# AD8367.net
KiCad netlist of a schematic drawn in Altium Designer
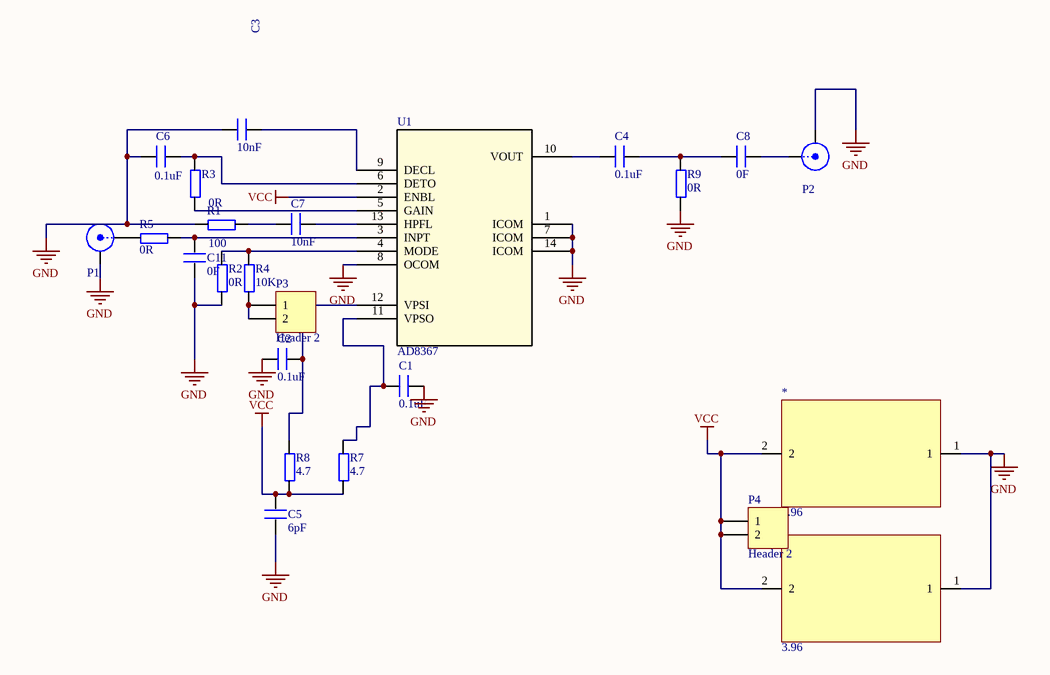
[diagram p0: AD8367.SchDoc]

(export (version "E")
  (design (tool "Eeschema 10.0.6"))
  (components
    (comp (ref "*") (value "3.96") (footprint "3.96") (libsource (lib "MYLIB") (part "3.96")))
    (comp (ref "1") (value "3.96") (footprint "3.96") (libsource (lib "MYLIB") (part "3.96")))
    (comp (ref "C1")
      (value "0.1uF")
      (footprint "0603C")
      (description "Capacitor")
      (libsource (lib "MYLIB") (part "C"))
    )
    (comp (ref "C2")
      (value "0.1uF")
      (footprint "0603C")
      (description "Capacitor")
      (libsource (lib "MYLIB") (part "C"))
    )
    (comp (ref "C3")
      (value "10nF")
      (footprint "0603C")
      (description "Capacitor")
      (libsource (lib "MYLIB") (part "C"))
    )
    (comp (ref "C4")
      (value "0.1uF")
      (footprint "0603C")
      (description "Capacitor")
      (libsource (lib "MYLIB") (part "C"))
    )
    (comp (ref "C5")
      (value "6pF")
      (footprint "C 0805_M")
      (description "Capacitor")
      (libsource (lib "MYLIB") (part "C"))
    )
    (comp (ref "C6")
      (value "0.1uF")
      (footprint "0603C")
      (description "Capacitor")
      (libsource (lib "MYLIB") (part "C"))
    )
    (comp (ref "C7")
      (value "10nF")
      (footprint "0603C")
      (description "Capacitor")
      (libsource (lib "MYLIB") (part "C"))
    )
    (comp (ref "C8")
      (value "0F")
      (footprint "0603C")
      (description "Capacitor")
      (libsource (lib "MYLIB") (part "C"))
    )
    (comp (ref "C11")
      (value "0F")
      (footprint "0603C")
      (description "Capacitor")
      (libsource (lib "MYLIB") (part "C"))
    )
    (comp (ref "P1")
      (value "SMA")
      (footprint "SMA-V")
      (description "SMA Connector")
      (libsource (lib "MYLIB") (part "SMA"))
    )
    (comp (ref "P2")
      (value "SMA")
      (footprint "SMA-V")
      (description "SMA Connector")
      (libsource (lib "MYLIB") (part "SMA"))
    )
    (comp (ref "P3")
      (value "Header 2")
      (footprint "HDR1X2")
      (description "Header, 2-Pin")
      (fields (field (name "PUBLISHER") "Altium Limited"))
      (libsource (lib "Miscellaneous Connectors") (part "Header 2"))
    )
    (comp (ref "P4")
      (value "Header 2")
      (footprint "HDR1X2")
      (description "Header, 2-Pin")
      (fields (field (name "PUBLISHER") "Altium Limited"))
      (libsource (lib "Miscellaneous Connectors") (part "Header 2"))
    )
    (comp (ref "R1")
      (value "100")
      (footprint "0603R")
      (description "Resistor")
      (libsource (lib "MYLIB") (part "Resistor"))
    )
    (comp (ref "R2")
      (value "0R")
      (footprint "0603R")
      (description "Resistor")
      (libsource (lib "MYLIB") (part "Resistor"))
    )
    (comp (ref "R3")
      (value "0R")
      (footprint "0603R")
      (description "Resistor")
      (libsource (lib "MYLIB") (part "Resistor"))
    )
    (comp (ref "R4")
      (value "10K")
      (footprint "0603R")
      (description "Resistor")
      (libsource (lib "MYLIB") (part "Resistor"))
    )
    (comp (ref "R5")
      (value "0R")
      (footprint "0603R")
      (description "Resistor")
      (libsource (lib "MYLIB") (part "Resistor"))
    )
    (comp (ref "R7")
      (value "4.7")
      (footprint "0603R")
      (description "Resistor")
      (libsource (lib "MYLIB") (part "Resistor"))
    )
    (comp (ref "R8")
      (value "4.7")
      (footprint "0603R")
      (description "Resistor")
      (libsource (lib "MYLIB") (part "Resistor"))
    )
    (comp (ref "R9")
      (value "0R")
      (footprint "0603R")
      (description "Resistor")
      (libsource (lib "MYLIB") (part "Resistor"))
    )
    (comp (ref "U1")
      (value "AD8367")
      (footprint "RU_14")
      (description "500 MHz 、45dB线性dB可变增益放大器")
      (fields
        (field (name "MANUFACTURER_PART_NUMBER") "AD8367ARUZ")
        (field (name "COPYRIGHT") "Copyright (C) 2018 Accelerated Designs. All rights reserved")
      )
      (libsource (lib "MYLIB") (part "AD8367"))
    )
  )
  (nets
    (net (code "1") (name "GND") (class "Default")
      (node (ref "*") (pin "1") (pinfunction "1_1") (pintype "passive"))
      (node (ref "1") (pin "1") (pinfunction "1_1") (pintype "passive"))
      (node (ref "C1") (pin "1") (pintype "passive"))
      (node (ref "C11") (pin "2") (pintype "passive"))
      (node (ref "C2") (pin "2") (pintype "passive"))
      (node (ref "C3") (pin "1") (pintype "passive"))
      (node (ref "C5") (pin "1") (pintype "passive"))
      (node (ref "C6") (pin "1") (pintype "passive"))
      (node (ref "P1") (pin "2") (pinfunction "Y_2") (pintype "passive"))
      (node (ref "P2") (pin "2") (pinfunction "Y_2") (pintype "passive"))
      (node (ref "R1") (pin "1") (pintype "passive"))
      (node (ref "R2") (pin "1") (pintype "passive"))
      (node (ref "R9") (pin "1") (pintype "passive"))
      (node (ref "U1") (pin "1") (pinfunction "ICOM_1") (pintype "passive"))
      (node (ref "U1") (pin "14") (pinfunction "ICOM_14") (pintype "passive"))
      (node (ref "U1") (pin "7") (pinfunction "ICOM_7") (pintype "passive"))
      (node (ref "U1") (pin "8") (pinfunction "OCOM_8") (pintype "passive"))
    )
    (net (code "2") (name "Net-(C4-Pad2)") (class "Default")
      (node (ref "C4") (pin "2") (pintype "passive"))
      (node (ref "C8") (pin "1") (pintype "passive"))
      (node (ref "R9") (pin "2") (pintype "passive"))
    )
    (net (code "3") (name "Net-(C7-Pad1)") (class "Default")
      (node (ref "C7") (pin "1") (pintype "passive"))
      (node (ref "R1") (pin "2") (pintype "passive"))
    )
    (net (code "4") (name "Net-(P1-X)") (class "Default")
      (node (ref "P1") (pin "1") (pinfunction "X_1") (pintype "passive"))
      (node (ref "R5") (pin "1") (pintype "passive"))
    )
    (net (code "5") (name "Net-(P2-X)") (class "Default")
      (node (ref "C8") (pin "2") (pintype "passive"))
      (node (ref "P2") (pin "1") (pinfunction "X_1") (pintype "passive"))
    )
    (net (code "6") (name "Net-(P3-Pad1)") (class "Default")
      (node (ref "P3") (pin "1") (pinfunction "1_1") (pintype "passive"))
      (node (ref "P3") (pin "2") (pinfunction "2_2") (pintype "passive"))
      (node (ref "R4") (pin "1") (pintype "passive"))
    )
    (net (code "7") (name "Net-(U1-DECL)") (class "Default")
      (node (ref "C3") (pin "2") (pintype "passive"))
      (node (ref "U1") (pin "9") (pinfunction "DECL_9") (pintype "passive"))
    )
    (net (code "8") (name "Net-(U1-DETO)") (class "Default")
      (node (ref "C6") (pin "2") (pintype "passive"))
      (node (ref "R3") (pin "2") (pintype "passive"))
      (node (ref "U1") (pin "6") (pinfunction "DETO_6") (pintype "passive"))
    )
    (net (code "9") (name "Net-(U1-GAIN)") (class "Default")
      (node (ref "R3") (pin "1") (pintype "passive"))
      (node (ref "U1") (pin "5") (pinfunction "GAIN_5") (pintype "passive"))
    )
    (net (code "10") (name "Net-(U1-HPFL)") (class "Default")
      (node (ref "C7") (pin "2") (pintype "passive"))
      (node (ref "U1") (pin "13") (pinfunction "HPFL_13") (pintype "passive"))
    )
    (net (code "11") (name "Net-(U1-INPT)") (class "Default")
      (node (ref "C11") (pin "1") (pintype "passive"))
      (node (ref "R5") (pin "2") (pintype "passive"))
      (node (ref "U1") (pin "3") (pinfunction "INPT_3") (pintype "passive"))
    )
    (net (code "12") (name "Net-(U1-MODE)") (class "Default")
      (node (ref "R2") (pin "2") (pintype "passive"))
      (node (ref "R4") (pin "2") (pintype "passive"))
      (node (ref "U1") (pin "4") (pinfunction "MODE_4") (pintype "passive"))
    )
    (net (code "13") (name "Net-(U1-VOUT)") (class "Default")
      (node (ref "C4") (pin "1") (pintype "passive"))
      (node (ref "U1") (pin "10") (pinfunction "VOUT_10") (pintype "passive"))
    )
    (net (code "14") (name "Net-(U1-VPSI)") (class "Default")
      (node (ref "C2") (pin "1") (pintype "passive"))
      (node (ref "R8") (pin "2") (pintype "passive"))
      (node (ref "U1") (pin "12") (pinfunction "VPSI_12") (pintype "power_in"))
    )
    (net (code "15") (name "Net-(U1-VPSO)") (class "Default")
      (node (ref "C1") (pin "2") (pintype "passive"))
      (node (ref "R7") (pin "2") (pintype "passive"))
      (node (ref "U1") (pin "11") (pinfunction "VPSO_11") (pintype "power_in"))
    )
    (net (code "16") (name "VCC") (class "Default")
      (node (ref "*") (pin "2") (pinfunction "2_2") (pintype "passive"))
      (node (ref "1") (pin "2") (pinfunction "2_2") (pintype "passive"))
      (node (ref "C5") (pin "2") (pintype "passive"))
      (node (ref "P4") (pin "1") (pinfunction "1_1") (pintype "passive"))
      (node (ref "P4") (pin "2") (pinfunction "2_2") (pintype "passive"))
      (node (ref "R7") (pin "1") (pintype "passive"))
      (node (ref "R8") (pin "1") (pintype "passive"))
      (node (ref "U1") (pin "2") (pinfunction "ENBL_2") (pintype "passive"))
    )
  )
)
